# sh.net
KiCad netlist of a schematic drawn in EAGLE
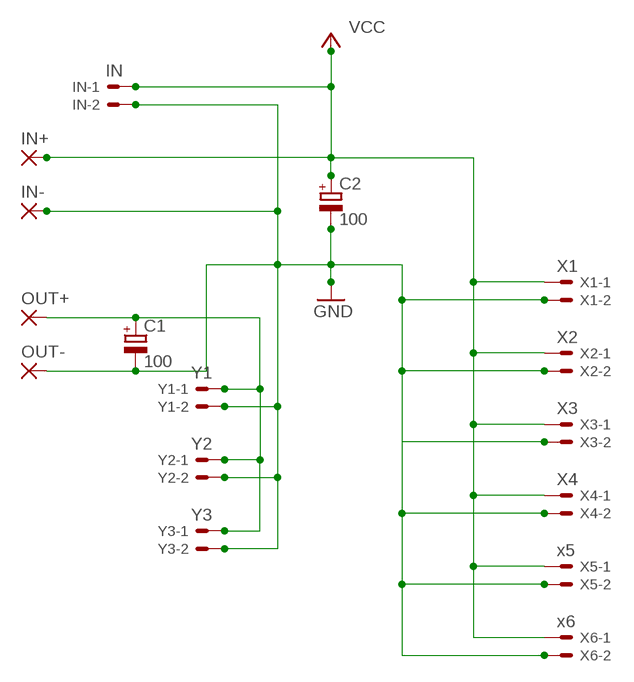
[diagram p0: schematic, sheet 1]

(export (version "E")
  (design (tool "Eeschema 10.0.6"))
  (components
    (comp (ref "C1")
      (value "100")
      (footprint "eagle-import:E5-10,5")
      (libsource (lib "eagle-import") (part "CPOL-EUE5-10.5"))
    )
    (comp (ref "C2")
      (value "100")
      (footprint "eagle-import:E5-10,5")
      (libsource (lib "eagle-import") (part "CPOL-EUE5-10.5"))
    )
    (comp (ref "IN")
      (value "IN")
      (footprint "eagle-import:70543-02")
      (fields (field (name "MF") "MOLEX"))
      (libsource (lib "eagle-import") (part "con-molex_165_C-GRID-02-70543"))
    )
    (comp (ref "IN+")
      (value "3,17/1,3")
      (footprint "eagle-import:3,17_1,3")
      (libsource (lib "eagle-import") (part "3,17/1,3"))
    )
    (comp (ref "IN-")
      (value "3,17/1,3")
      (footprint "eagle-import:3,17_1,3")
      (libsource (lib "eagle-import") (part "3,17/1,3"))
    )
    (comp (ref "OUT+")
      (value "3,17/1,3")
      (footprint "eagle-import:3,17_1,3")
      (libsource (lib "eagle-import") (part "3,17/1,3"))
    )
    (comp (ref "OUT-")
      (value "3,17/1,3")
      (footprint "eagle-import:3,17_1,3")
      (libsource (lib "eagle-import") (part "3,17/1,3"))
    )
    (comp (ref "X1")
      (value "X1")
      (footprint "eagle-import:70543-02")
      (libsource (lib "eagle-import") (part "C-GRID-02-70543"))
    )
    (comp (ref "X2")
      (value "X2")
      (footprint "eagle-import:70543-02")
      (libsource (lib "eagle-import") (part "C-GRID-02-70543"))
    )
    (comp (ref "X3")
      (value "X3")
      (footprint "eagle-import:70543-02")
      (libsource (lib "eagle-import") (part "C-GRID-02-70543"))
    )
    (comp (ref "X4")
      (value "X4")
      (footprint "eagle-import:70543-02")
      (libsource (lib "eagle-import") (part "C-GRID-02-70543"))
    )
    (comp (ref "X5")
      (value "x5")
      (footprint "eagle-import:70543-02")
      (libsource (lib "eagle-import") (part "C-GRID-02-70543"))
    )
    (comp (ref "X6")
      (value "x6")
      (footprint "eagle-import:70543-02")
      (libsource (lib "eagle-import") (part "C-GRID-02-70543"))
    )
    (comp (ref "Y1")
      (value "Y1")
      (footprint "eagle-import:70543-02")
      (fields (field (name "MF") "MOLEX"))
      (libsource (lib "eagle-import") (part "con-molex_165_C-GRID-02-70543"))
    )
    (comp (ref "Y2")
      (value "Y2")
      (footprint "eagle-import:70543-02")
      (fields (field (name "MF") "MOLEX"))
      (libsource (lib "eagle-import") (part "con-molex_165_C-GRID-02-70543"))
    )
    (comp (ref "Y3")
      (value "Y3")
      (footprint "eagle-import:70543-02")
      (fields (field (name "MF") "MOLEX"))
      (libsource (lib "eagle-import") (part "con-molex_165_C-GRID-02-70543"))
    )
  )
  (nets
    (net (code "1") (name "GND") (class "Default")
      (node (ref "C1") (pin "-") (pinfunction "-_-") (pintype "passive"))
      (node (ref "C2") (pin "-") (pinfunction "-_-") (pintype "passive"))
      (node (ref "IN") (pin "2") (pinfunction "S_2") (pintype "passive"))
      (node (ref "IN-") (pin "1") (pinfunction "P_1") (pintype "passive"))
      (node (ref "OUT-") (pin "1") (pinfunction "P_1") (pintype "passive"))
      (node (ref "X1") (pin "2") (pinfunction "S_2") (pintype "passive"))
      (node (ref "X2") (pin "2") (pinfunction "S_2") (pintype "passive"))
      (node (ref "X3") (pin "2") (pinfunction "S_2") (pintype "passive"))
      (node (ref "X4") (pin "2") (pinfunction "S_2") (pintype "passive"))
      (node (ref "X5") (pin "2") (pinfunction "S_2") (pintype "passive"))
      (node (ref "X6") (pin "2") (pinfunction "S_2") (pintype "passive"))
      (node (ref "Y1") (pin "2") (pinfunction "S_2") (pintype "passive"))
      (node (ref "Y2") (pin "2") (pinfunction "S_2") (pintype "passive"))
      (node (ref "Y3") (pin "2") (pinfunction "S_2") (pintype "passive"))
    )
    (net (code "2") (name "Net-(OUT+-P)") (class "Default")
      (node (ref "C1") (pin "+") (pinfunction "+_+") (pintype "passive"))
      (node (ref "OUT+") (pin "1") (pinfunction "P_1") (pintype "passive"))
      (node (ref "Y1") (pin "1") (pinfunction "S_1") (pintype "passive"))
      (node (ref "Y2") (pin "1") (pinfunction "S_1") (pintype "passive"))
      (node (ref "Y3") (pin "1") (pinfunction "S_1") (pintype "passive"))
    )
    (net (code "3") (name "VCC") (class "Default")
      (node (ref "C2") (pin "+") (pinfunction "+_+") (pintype "passive"))
      (node (ref "IN") (pin "1") (pinfunction "S_1") (pintype "passive"))
      (node (ref "IN+") (pin "1") (pinfunction "P_1") (pintype "passive"))
      (node (ref "X1") (pin "1") (pinfunction "S_1") (pintype "passive"))
      (node (ref "X2") (pin "1") (pinfunction "S_1") (pintype "passive"))
      (node (ref "X3") (pin "1") (pinfunction "S_1") (pintype "passive"))
      (node (ref "X4") (pin "1") (pinfunction "S_1") (pintype "passive"))
      (node (ref "X5") (pin "1") (pinfunction "S_1") (pintype "passive"))
      (node (ref "X6") (pin "1") (pinfunction "S_1") (pintype "passive"))
    )
  )
)
